# Driver.net
KiCad netlist of a schematic drawn in Altium Designer
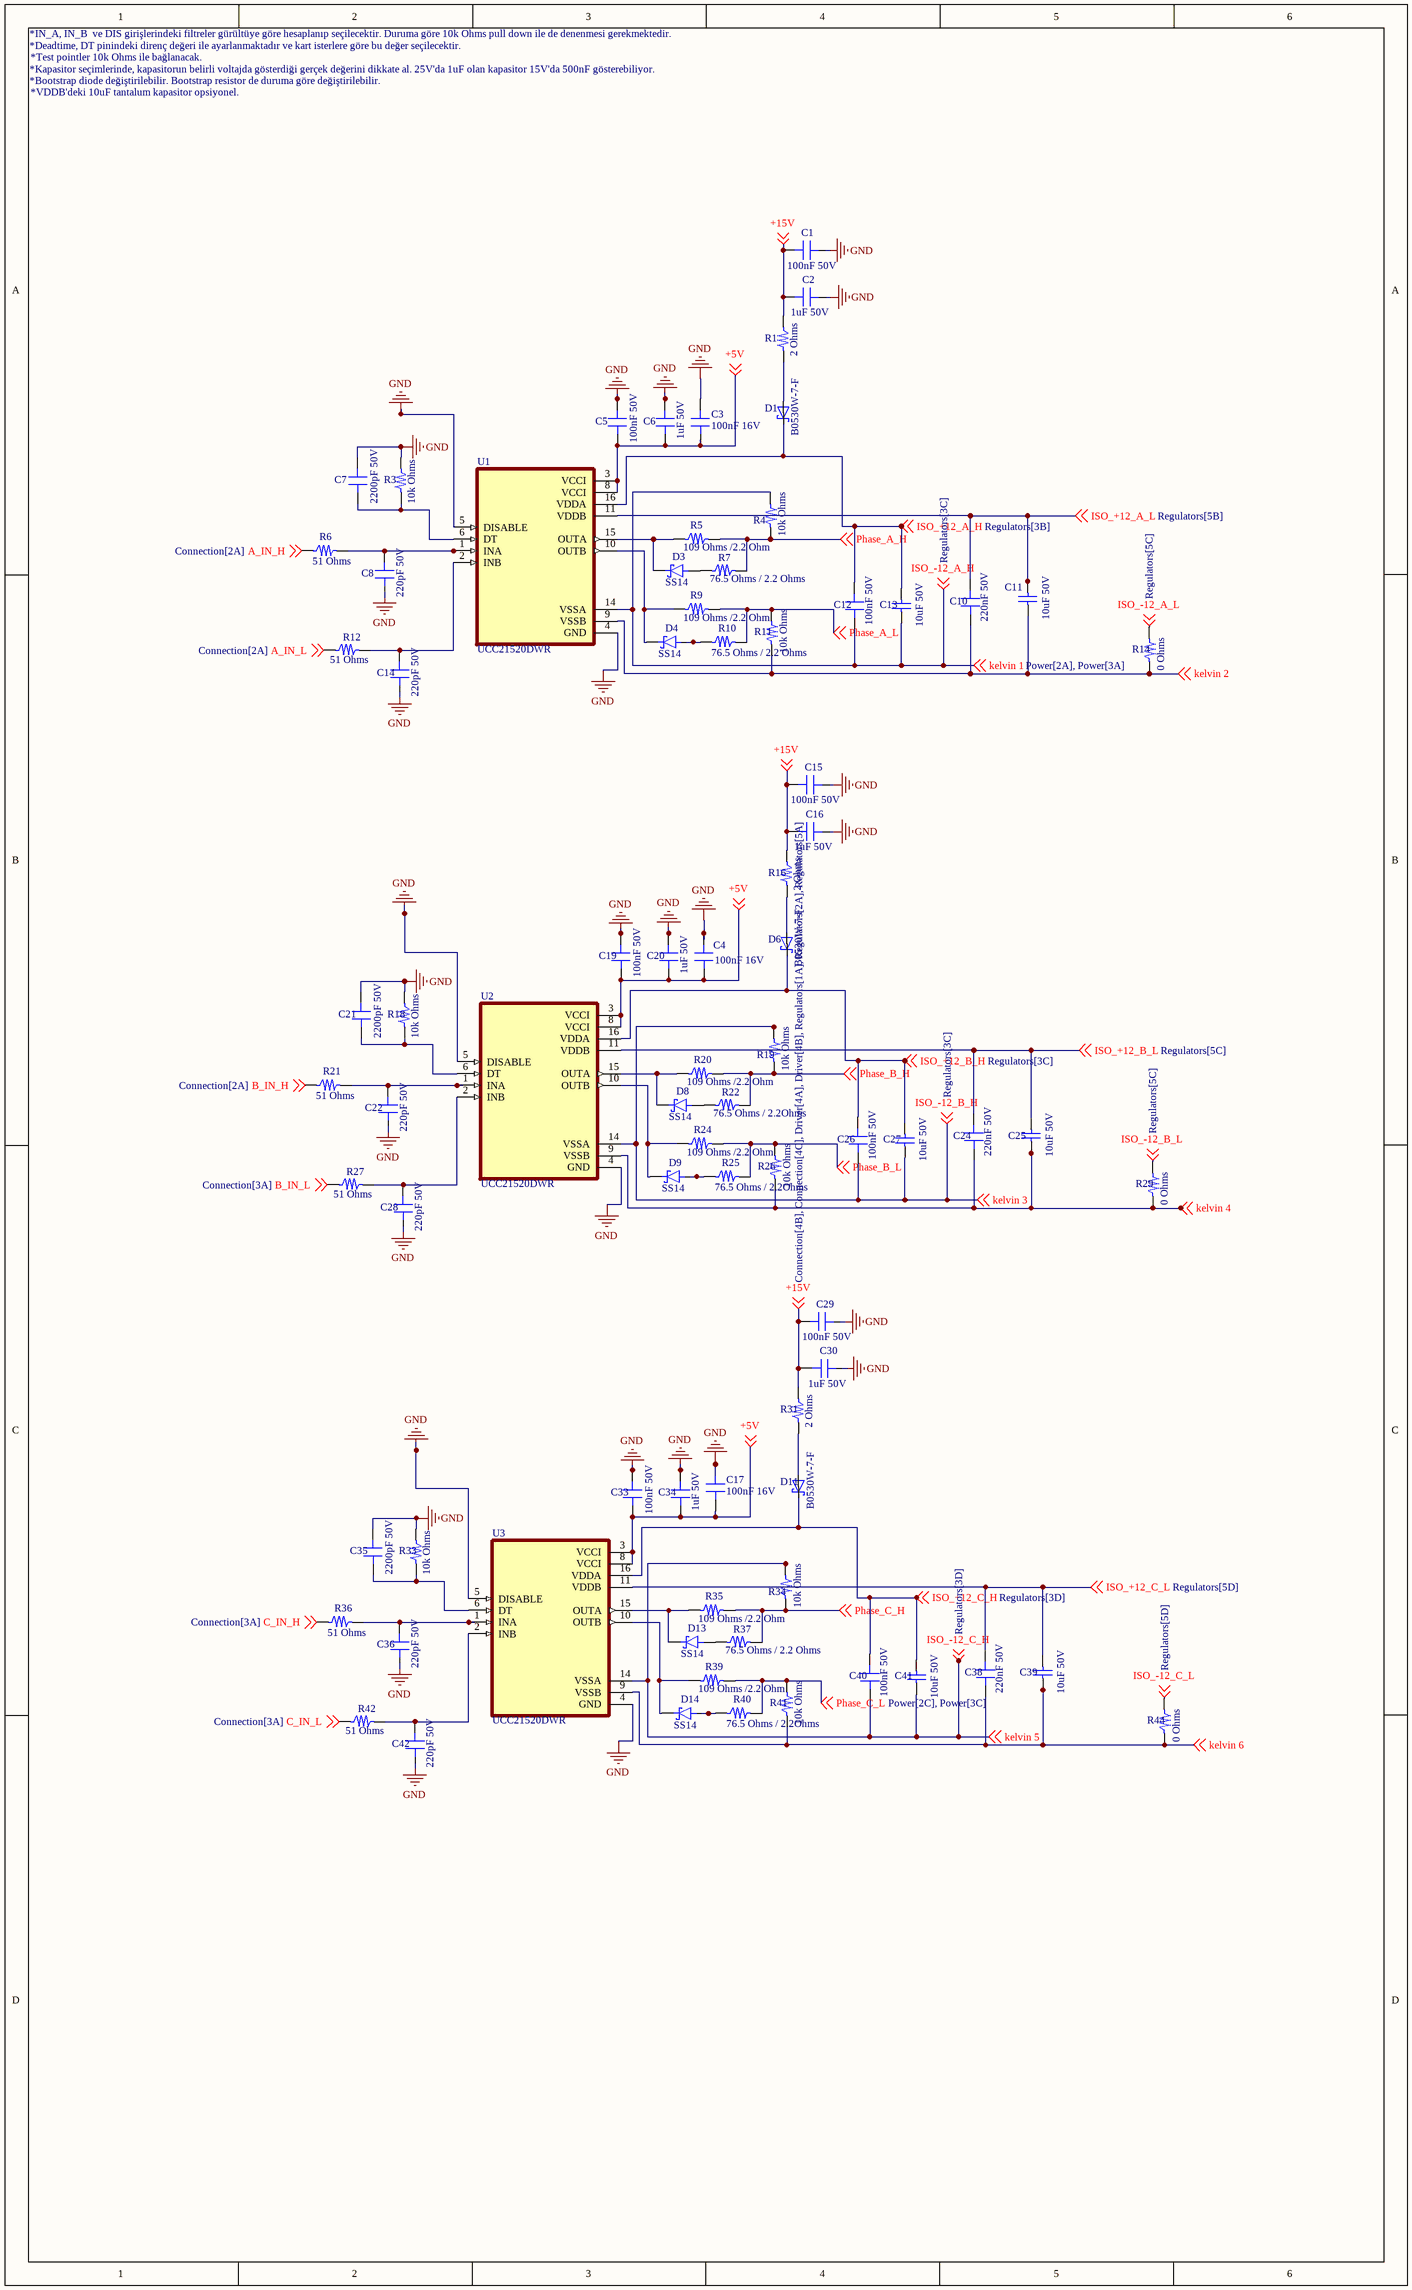
[diagram p0: Driver.SchDoc]

(export (version "E")
  (design (tool "Eeschema 10.0.6"))
  (components
    (comp (ref "C1")
      (value "100nF 50V")
      (footprint "0805_CAP")
      (libsource (lib "HidroanaSCHLib") (part "CAP_0805"))
    )
    (comp (ref "C2")
      (value "1uF 50V")
      (footprint "0805_CAP")
      (libsource (lib "HidroanaSCHLib") (part "CAP_0805"))
    )
    (comp (ref "C3")
      (value "100nF 16V")
      (footprint "0805_CAP")
      (libsource (lib "HidroanaSCHLib1") (part "CAP_0805"))
    )
    (comp (ref "C4")
      (value "100nF 16V")
      (footprint "0805_CAP")
      (libsource (lib "HidroanaSCHLib1") (part "CAP_0805"))
    )
    (comp (ref "C5")
      (value "100nF 50V")
      (footprint "0603_CAP")
      (description "CL10B105KO8NNNC - MLCC (1608) 0603 1uF 16VDC ±10% X7R")
      (libsource (lib "HidroanaSCHLib") (part "CAP_0603"))
    )
    (comp (ref "C6")
      (value "1uF 50V")
      (footprint "0603_CAP")
      (description "CL10B105KO8NNNC - MLCC (1608) 0603 1uF 16VDC ±10% X7R")
      (libsource (lib "HidroanaSCHLib") (part "CAP_0603"))
    )
    (comp (ref "C7")
      (value "2200pF 50V")
      (footprint "0603_CAP")
      (description "CL10B105KO8NNNC - MLCC (1608) 0603 1uF 16VDC ±10% X7R")
      (libsource (lib "HidroanaSCHLib") (part "CAP_0603"))
    )
    (comp (ref "C8")
      (value "220pF 50V")
      (footprint "0603_CAP")
      (description "CL10B105KO8NNNC - MLCC (1608) 0603 1uF 16VDC ±10% X7R")
      (libsource (lib "HidroanaSCHLib") (part "CAP_0603"))
    )
    (comp (ref "C10")
      (value "220nF 50V")
      (footprint "0805_CAP")
      (libsource (lib "HidroanaSCHLib") (part "CAP_0805"))
    )
    (comp (ref "C11")
      (value "10uF 50V")
      (footprint "WCAP-CSGP_1210_L3.2W2.5H0.95")
      (description "WCAP-CSGP Multilayer Ceramic Chip Capacitor, General Purpose, size 1210, NP0, 2.2nF, 50V")
      (fields
        (field (name "MANUFACTURER PART NUMBER") "885012009019")
        (field (name "MANUFACTURER") "Wurth Elektronik")
      )
      (libsource (lib "Altium_WCAP-CSGP (rev24c)") (part "885012009019"))
    )
    (comp (ref "C12")
      (value "100nF 50V")
      (footprint "0805_CAP")
      (libsource (lib "HidroanaSCHLib") (part "CAP_0805"))
    )
    (comp (ref "C13")
      (value "10uF 50V")
      (footprint "WCAP-CSGP_1210_L3.2W2.5H0.95")
      (description "WCAP-CSGP Multilayer Ceramic Chip Capacitor, General Purpose, size 1210, NP0, 2.2nF, 50V")
      (fields
        (field (name "MANUFACTURER PART NUMBER") "885012009019")
        (field (name "MANUFACTURER") "Wurth Elektronik")
      )
      (libsource (lib "Altium_WCAP-CSGP (rev24c)") (part "885012009019"))
    )
    (comp (ref "C14")
      (value "220pF 50V")
      (footprint "0603_CAP")
      (description "CL10B105KO8NNNC - MLCC (1608) 0603 1uF 16VDC ±10% X7R")
      (libsource (lib "HidroanaSCHLib") (part "CAP_0603"))
    )
    (comp (ref "C15")
      (value "100nF 50V")
      (footprint "0805_CAP")
      (libsource (lib "HidroanaSCHLib") (part "CAP_0805"))
    )
    (comp (ref "C16")
      (value "1uF 50V")
      (footprint "0805_CAP")
      (libsource (lib "HidroanaSCHLib") (part "CAP_0805"))
    )
    (comp (ref "C17")
      (value "100nF 16V")
      (footprint "0805_CAP")
      (libsource (lib "HidroanaSCHLib1") (part "CAP_0805"))
    )
    (comp (ref "C19")
      (value "100nF 50V")
      (footprint "0603_CAP")
      (description "CL10B105KO8NNNC - MLCC (1608) 0603 1uF 16VDC ±10% X7R")
      (libsource (lib "HidroanaSCHLib") (part "CAP_0603"))
    )
    (comp (ref "C20")
      (value "1uF 50V")
      (footprint "0603_CAP")
      (description "CL10B105KO8NNNC - MLCC (1608) 0603 1uF 16VDC ±10% X7R")
      (libsource (lib "HidroanaSCHLib") (part "CAP_0603"))
    )
    (comp (ref "C21")
      (value "2200pF 50V")
      (footprint "0603_CAP")
      (description "CL10B105KO8NNNC - MLCC (1608) 0603 1uF 16VDC ±10% X7R")
      (libsource (lib "HidroanaSCHLib") (part "CAP_0603"))
    )
    (comp (ref "C22")
      (value "220pF 50V")
      (footprint "0603_CAP")
      (description "CL10B105KO8NNNC - MLCC (1608) 0603 1uF 16VDC ±10% X7R")
      (libsource (lib "HidroanaSCHLib") (part "CAP_0603"))
    )
    (comp (ref "C24")
      (value "220nF 50V")
      (footprint "0805_CAP")
      (libsource (lib "HidroanaSCHLib") (part "CAP_0805"))
    )
    (comp (ref "C25")
      (value "10uF 50V")
      (footprint "WCAP-CSGP_1210_L3.2W2.5H0.95")
      (description "WCAP-CSGP Multilayer Ceramic Chip Capacitor, General Purpose, size 1210, NP0, 2.2nF, 50V")
      (fields
        (field (name "MANUFACTURER PART NUMBER") "885012009019")
        (field (name "MANUFACTURER") "Wurth Elektronik")
      )
      (libsource (lib "Altium_WCAP-CSGP (rev24c)") (part "885012009019"))
    )
    (comp (ref "C26")
      (value "100nF 50V")
      (footprint "0805_CAP")
      (libsource (lib "HidroanaSCHLib") (part "CAP_0805"))
    )
    (comp (ref "C27")
      (value "10uF 50V")
      (footprint "WCAP-CSGP_1210_L3.2W2.5H0.95")
      (description "WCAP-CSGP Multilayer Ceramic Chip Capacitor, General Purpose, size 1210, NP0, 2.2nF, 50V")
      (fields
        (field (name "MANUFACTURER PART NUMBER") "885012009019")
        (field (name "MANUFACTURER") "Wurth Elektronik")
      )
      (libsource (lib "Altium_WCAP-CSGP (rev24c)") (part "885012009019"))
    )
    (comp (ref "C28")
      (value "220pF 50V")
      (footprint "0603_CAP")
      (description "CL10B105KO8NNNC - MLCC (1608) 0603 1uF 16VDC ±10% X7R")
      (libsource (lib "HidroanaSCHLib") (part "CAP_0603"))
    )
    (comp (ref "C29")
      (value "100nF 50V")
      (footprint "0805_CAP")
      (libsource (lib "HidroanaSCHLib") (part "CAP_0805"))
    )
    (comp (ref "C30")
      (value "1uF 50V")
      (footprint "0805_CAP")
      (libsource (lib "HidroanaSCHLib") (part "CAP_0805"))
    )
    (comp (ref "C33")
      (value "100nF 50V")
      (footprint "0603_CAP")
      (description "CL10B105KO8NNNC - MLCC (1608) 0603 1uF 16VDC ±10% X7R")
      (libsource (lib "HidroanaSCHLib") (part "CAP_0603"))
    )
    (comp (ref "C34")
      (value "1uF 50V")
      (footprint "0603_CAP")
      (description "CL10B105KO8NNNC - MLCC (1608) 0603 1uF 16VDC ±10% X7R")
      (libsource (lib "HidroanaSCHLib") (part "CAP_0603"))
    )
    (comp (ref "C35")
      (value "2200pF 50V")
      (footprint "0603_CAP")
      (description "CL10B105KO8NNNC - MLCC (1608) 0603 1uF 16VDC ±10% X7R")
      (libsource (lib "HidroanaSCHLib") (part "CAP_0603"))
    )
    (comp (ref "C36")
      (value "220pF 50V")
      (footprint "0603_CAP")
      (description "CL10B105KO8NNNC - MLCC (1608) 0603 1uF 16VDC ±10% X7R")
      (libsource (lib "HidroanaSCHLib") (part "CAP_0603"))
    )
    (comp (ref "C38")
      (value "220nF 50V")
      (footprint "0805_CAP")
      (libsource (lib "HidroanaSCHLib") (part "CAP_0805"))
    )
    (comp (ref "C39")
      (value "10uF 50V")
      (footprint "WCAP-CSGP_1210_L3.2W2.5H0.95")
      (description "WCAP-CSGP Multilayer Ceramic Chip Capacitor, General Purpose, size 1210, NP0, 2.2nF, 50V")
      (fields
        (field (name "MANUFACTURER PART NUMBER") "885012009019")
        (field (name "MANUFACTURER") "Wurth Elektronik")
      )
      (libsource (lib "Altium_WCAP-CSGP (rev24c)") (part "885012009019"))
    )
    (comp (ref "C40")
      (value "100nF 50V")
      (footprint "0805_CAP")
      (libsource (lib "HidroanaSCHLib") (part "CAP_0805"))
    )
    (comp (ref "C41")
      (value "10uF 50V")
      (footprint "WCAP-CSGP_1210_L3.2W2.5H0.95")
      (description "WCAP-CSGP Multilayer Ceramic Chip Capacitor, General Purpose, size 1210, NP0, 2.2nF, 50V")
      (fields
        (field (name "MANUFACTURER PART NUMBER") "885012009019")
        (field (name "MANUFACTURER") "Wurth Elektronik")
      )
      (libsource (lib "Altium_WCAP-CSGP (rev24c)") (part "885012009019"))
    )
    (comp (ref "C42")
      (value "220pF 50V")
      (footprint "0603_CAP")
      (description "CL10B105KO8NNNC - MLCC (1608) 0603 1uF 16VDC ±10% X7R")
      (libsource (lib "HidroanaSCHLib") (part "CAP_0603"))
    )
    (comp (ref "D1")
      (value "B0530W-7-F")
      (footprint "DO-214AC")
      (description "Diode Schottky 40 V 1A Surface Mount DO-214AC (SMA)")
      (fields (field (name "MF") "ON Semiconductor") (field (name "MP") "SS14"))
      (libsource (lib "SS14") (part "SS14"))
    )
    (comp (ref "D3")
      (value "SS14")
      (footprint "SOD3715X145N")
      (description "Diode Schottky 30V 500mA Surface Mount SOD-123")
      (fields (field (name "MP") "B0530W-7-F") (field (name "MF") "Diodes Inc."))
      (libsource (lib "B0530W-7-F") (part "B0530W-7-F"))
    )
    (comp (ref "D4")
      (value "SS14")
      (footprint "SOD3715X145N")
      (description "Diode Schottky 30V 500mA Surface Mount SOD-123")
      (fields (field (name "MP") "B0530W-7-F") (field (name "MF") "Diodes Inc."))
      (libsource (lib "B0530W-7-F") (part "B0530W-7-F"))
    )
    (comp (ref "D6")
      (value "B0530W-7-F")
      (footprint "DO-214AC")
      (description "Diode Schottky 40 V 1A Surface Mount DO-214AC (SMA)")
      (fields (field (name "MF") "ON Semiconductor") (field (name "MP") "SS14"))
      (libsource (lib "SS14") (part "SS14"))
    )
    (comp (ref "D8")
      (value "SS14")
      (footprint "SOD3715X145N")
      (description "Diode Schottky 30V 500mA Surface Mount SOD-123")
      (fields (field (name "MP") "B0530W-7-F") (field (name "MF") "Diodes Inc."))
      (libsource (lib "B0530W-7-F") (part "B0530W-7-F"))
    )
    (comp (ref "D9")
      (value "SS14")
      (footprint "SOD3715X145N")
      (description "Diode Schottky 30V 500mA Surface Mount SOD-123")
      (fields (field (name "MP") "B0530W-7-F") (field (name "MF") "Diodes Inc."))
      (libsource (lib "B0530W-7-F") (part "B0530W-7-F"))
    )
    (comp (ref "D11")
      (value "B0530W-7-F")
      (footprint "DO-214AC")
      (description "Diode Schottky 40 V 1A Surface Mount DO-214AC (SMA)")
      (fields (field (name "MF") "ON Semiconductor") (field (name "MP") "SS14"))
      (libsource (lib "SS14") (part "SS14"))
    )
    (comp (ref "D13")
      (value "SS14")
      (footprint "SOD3715X145N")
      (description "Diode Schottky 30V 500mA Surface Mount SOD-123")
      (fields (field (name "MP") "B0530W-7-F") (field (name "MF") "Diodes Inc."))
      (libsource (lib "B0530W-7-F") (part "B0530W-7-F"))
    )
    (comp (ref "D14")
      (value "SS14")
      (footprint "SOD3715X145N")
      (description "Diode Schottky 30V 500mA Surface Mount SOD-123")
      (fields (field (name "MP") "B0530W-7-F") (field (name "MF") "Diodes Inc."))
      (libsource (lib "B0530W-7-F") (part "B0530W-7-F"))
    )
    (comp (ref "R1")
      (value "2 Ohms")
      (footprint "0805_RES")
      (description "0805")
      (fields (field (name "POWER") "1/8 W"))
      (libsource (lib "HidroanaSCHLib") (part "RES_0805"))
    )
    (comp (ref "R3")
      (value "10k Ohms")
      (footprint "0603_RES")
      (libsource (lib "HidroanaSCHLib") (part "1k Ohms"))
    )
    (comp (ref "R4")
      (value "10k Ohms")
      (footprint "0805_RES")
      (description "0805")
      (fields (field (name "POWER") "1/8 W"))
      (libsource (lib "HidroanaSCHLib") (part "RES_0805"))
    )
    (comp (ref "R5")
      (value "109 Ohms /2.2 Ohm")
      (footprint "0805_RES")
      (description "0805")
      (fields (field (name "POWER") "1/8 W"))
      (libsource (lib "HidroanaSCHLib") (part "RES_0805"))
    )
    (comp (ref "R6")
      (value "51 Ohms")
      (footprint "0603_RES")
      (libsource (lib "HidroanaSCHLib") (part "1k Ohms"))
    )
    (comp (ref "R7")
      (value "76.5 Ohms / 2.2 Ohms")
      (footprint "0805_RES")
      (description "0805")
      (fields (field (name "POWER") "1/8 W"))
      (libsource (lib "HidroanaSCHLib") (part "RES_0805"))
    )
    (comp (ref "R9")
      (value "109 Ohms /2.2 Ohm")
      (footprint "0805_RES")
      (description "0805")
      (fields (field (name "POWER") "1/8 W"))
      (libsource (lib "HidroanaSCHLib") (part "RES_0805"))
    )
    (comp (ref "R10")
      (value "76.5 Ohms / 2.2 Ohms")
      (footprint "0805_RES")
      (description "0805")
      (fields (field (name "POWER") "1/8 W"))
      (libsource (lib "HidroanaSCHLib") (part "RES_0805"))
    )
    (comp (ref "R11")
      (value "10k Ohms")
      (footprint "0805_RES")
      (description "0805")
      (fields (field (name "POWER") "1/8 W"))
      (libsource (lib "HidroanaSCHLib") (part "RES_0805"))
    )
    (comp (ref "R12")
      (value "51 Ohms")
      (footprint "0603_RES")
      (libsource (lib "HidroanaSCHLib") (part "1k Ohms"))
    )
    (comp (ref "R14")
      (value "0 Ohms")
      (footprint "0805_RES")
      (description "0805")
      (fields (field (name "POWER") "1/8 W"))
      (libsource (lib "HidroanaSCHLib") (part "RES_0805"))
    )
    (comp (ref "R16")
      (value "2 Ohms")
      (footprint "0805_RES")
      (description "0805")
      (fields (field (name "POWER") "1/8 W"))
      (libsource (lib "HidroanaSCHLib") (part "RES_0805"))
    )
    (comp (ref "R18")
      (value "10k Ohms")
      (footprint "0603_RES")
      (libsource (lib "HidroanaSCHLib") (part "1k Ohms"))
    )
    (comp (ref "R19")
      (value "10k Ohms")
      (footprint "0805_RES")
      (description "0805")
      (fields (field (name "POWER") "1/8 W"))
      (libsource (lib "HidroanaSCHLib") (part "RES_0805"))
    )
    (comp (ref "R20")
      (value "109 Ohms /2.2 Ohm")
      (footprint "0805_RES")
      (description "0805")
      (fields (field (name "POWER") "1/8 W"))
      (libsource (lib "HidroanaSCHLib") (part "RES_0805"))
    )
    (comp (ref "R21")
      (value "51 Ohms")
      (footprint "0603_RES")
      (libsource (lib "HidroanaSCHLib") (part "1k Ohms"))
    )
    (comp (ref "R22")
      (value "76.5 Ohms / 2.2Ohms")
      (footprint "0805_RES")
      (description "0805")
      (fields (field (name "POWER") "1/8 W"))
      (libsource (lib "HidroanaSCHLib") (part "RES_0805"))
    )
    (comp (ref "R24")
      (value "109 Ohms /2.2 Ohm")
      (footprint "0805_RES")
      (description "0805")
      (fields (field (name "POWER") "1/8 W"))
      (libsource (lib "HidroanaSCHLib") (part "RES_0805"))
    )
    (comp (ref "R25")
      (value "76.5 Ohms / 2.2Ohms")
      (footprint "0805_RES")
      (description "0805")
      (fields (field (name "POWER") "1/8 W"))
      (libsource (lib "HidroanaSCHLib") (part "RES_0805"))
    )
    (comp (ref "R26")
      (value "10k Ohms")
      (footprint "0805_RES")
      (description "0805")
      (fields (field (name "POWER") "1/8 W"))
      (libsource (lib "HidroanaSCHLib") (part "RES_0805"))
    )
    (comp (ref "R27")
      (value "51 Ohms")
      (footprint "0603_RES")
      (libsource (lib "HidroanaSCHLib") (part "1k Ohms"))
    )
    (comp (ref "R29")
      (value "0 Ohms")
      (footprint "0805_RES")
      (description "0805")
      (fields (field (name "POWER") "1/8 W"))
      (libsource (lib "HidroanaSCHLib") (part "RES_0805"))
    )
    (comp (ref "R31")
      (value "2 Ohms")
      (footprint "0805_RES")
      (description "0805")
      (fields (field (name "POWER") "1/8 W"))
      (libsource (lib "HidroanaSCHLib") (part "RES_0805"))
    )
    (comp (ref "R33")
      (value "10k Ohms")
      (footprint "0603_RES")
      (libsource (lib "HidroanaSCHLib") (part "1k Ohms"))
    )
    (comp (ref "R34")
      (value "10k Ohms")
      (footprint "0805_RES")
      (description "0805")
      (fields (field (name "POWER") "1/8 W"))
      (libsource (lib "HidroanaSCHLib") (part "RES_0805"))
    )
    (comp (ref "R35")
      (value "109 Ohms /2.2 Ohm")
      (footprint "0805_RES")
      (description "0805")
      (fields (field (name "POWER") "1/8 W"))
      (libsource (lib "HidroanaSCHLib") (part "RES_0805"))
    )
    (comp (ref "R36")
      (value "51 Ohms")
      (footprint "0603_RES")
      (libsource (lib "HidroanaSCHLib") (part "1k Ohms"))
    )
    (comp (ref "R37")
      (value "76.5 Ohms / 2.2 Ohms")
      (footprint "0805_RES")
      (description "0805")
      (fields (field (name "POWER") "1/8 W"))
      (libsource (lib "HidroanaSCHLib") (part "RES_0805"))
    )
    (comp (ref "R39")
      (value "109 Ohms /2.2 Ohm")
      (footprint "0805_RES")
      (description "0805")
      (fields (field (name "POWER") "1/8 W"))
      (libsource (lib "HidroanaSCHLib") (part "RES_0805"))
    )
    (comp (ref "R40")
      (value "76.5 Ohms / 2.2Ohms")
      (footprint "0805_RES")
      (description "0805")
      (fields (field (name "POWER") "1/8 W"))
      (libsource (lib "HidroanaSCHLib") (part "RES_0805"))
    )
    (comp (ref "R41")
      (value "10k Ohms")
      (footprint "0805_RES")
      (description "0805")
      (fields (field (name "POWER") "1/8 W"))
      (libsource (lib "HidroanaSCHLib") (part "RES_0805"))
    )
    (comp (ref "R42")
      (value "51 Ohms")
      (footprint "0603_RES")
      (libsource (lib "HidroanaSCHLib") (part "1k Ohms"))
    )
    (comp (ref "R44")
      (value "0 Ohms")
      (footprint "0805_RES")
      (description "0805")
      (fields (field (name "POWER") "1/8 W"))
      (libsource (lib "HidroanaSCHLib") (part "RES_0805"))
    )
    (comp (ref "U1")
      (value "UCC21520DWR")
      (footprint "SOIC127P1030X265-16N")
      (fields (field (name "MF") "Texas Instruments"))
      (libsource (lib "UCC21520DWR") (part "UCC21520DWR"))
    )
    (comp (ref "U2")
      (value "UCC21520DWR")
      (footprint "SOIC127P1030X265-16N")
      (fields (field (name "MF") "Texas Instruments"))
      (libsource (lib "UCC21520DWR") (part "UCC21520DWR"))
    )
    (comp (ref "U3")
      (value "UCC21520DWR")
      (footprint "SOIC127P1030X265-16N")
      (fields (field (name "MF") "Texas Instruments"))
      (libsource (lib "UCC21520DWR") (part "UCC21520DWR"))
    )
  )
  (nets
    (net (code "1") (name "+5V") (class "Default")
      (node (ref "C17") (pin "2") (pinfunction "2_2") (pintype "passive"))
      (node (ref "C19") (pin "2") (pinfunction "2_2") (pintype "passive"))
      (node (ref "C20") (pin "2") (pinfunction "2_2") (pintype "passive"))
      (node (ref "C3") (pin "2") (pinfunction "2_2") (pintype "passive"))
      (node (ref "C33") (pin "2") (pinfunction "2_2") (pintype "passive"))
      (node (ref "C34") (pin "2") (pinfunction "2_2") (pintype "passive"))
      (node (ref "C4") (pin "2") (pinfunction "2_2") (pintype "passive"))
      (node (ref "C5") (pin "2") (pinfunction "2_2") (pintype "passive"))
      (node (ref "C6") (pin "2") (pinfunction "2_2") (pintype "passive"))
      (node (ref "U1") (pin "3") (pinfunction "VCCI_3") (pintype "power_in"))
      (node (ref "U1") (pin "8") (pinfunction "VCCI_8") (pintype "power_in"))
      (node (ref "U2") (pin "3") (pinfunction "VCCI_3") (pintype "power_in"))
      (node (ref "U2") (pin "8") (pinfunction "VCCI_8") (pintype "power_in"))
      (node (ref "U3") (pin "3") (pinfunction "VCCI_3") (pintype "power_in"))
      (node (ref "U3") (pin "8") (pinfunction "VCCI_8") (pintype "power_in"))
    )
    (net (code "2") (name "+15V") (class "Default")
      (node (ref "C1") (pin "2") (pinfunction "2_2") (pintype "passive"))
      (node (ref "C15") (pin "2") (pinfunction "2_2") (pintype "passive"))
      (node (ref "C16") (pin "2") (pinfunction "2_2") (pintype "passive"))
      (node (ref "C2") (pin "2") (pinfunction "2_2") (pintype "passive"))
      (node (ref "C29") (pin "2") (pinfunction "2_2") (pintype "passive"))
      (node (ref "C30") (pin "2") (pinfunction "2_2") (pintype "passive"))
      (node (ref "R1") (pin "2") (pintype "passive"))
      (node (ref "R16") (pin "2") (pintype "passive"))
      (node (ref "R31") (pin "2") (pintype "passive"))
    )
    (net (code "3") (name "A_IN_H") (class "Default") (node (ref "R6") (pin "1") (pintype "passive")))
    (net (code "4") (name "A_IN_L") (class "Default") (node (ref "R12") (pin "1") (pintype "passive")))
    (net (code "5") (name "B_IN_H") (class "Default") (node (ref "R21") (pin "1") (pintype "passive")))
    (net (code "6") (name "B_IN_L") (class "Default") (node (ref "R27") (pin "1") (pintype "passive")))
    (net (code "7") (name "C_IN_H") (class "Default") (node (ref "R36") (pin "1") (pintype "passive")))
    (net (code "8") (name "C_IN_L") (class "Default") (node (ref "R42") (pin "1") (pintype "passive")))
    (net (code "9") (name "GND") (class "Default")
      (node (ref "C1") (pin "1") (pinfunction "1_1") (pintype "passive"))
      (node (ref "C14") (pin "1") (pinfunction "1_1") (pintype "passive"))
      (node (ref "C15") (pin "1") (pinfunction "1_1") (pintype "passive"))
      (node (ref "C16") (pin "1") (pinfunction "1_1") (pintype "passive"))
      (node (ref "C17") (pin "1") (pinfunction "1_1") (pintype "passive"))
      (node (ref "C19") (pin "1") (pinfunction "1_1") (pintype "passive"))
      (node (ref "C2") (pin "1") (pinfunction "1_1") (pintype "passive"))
      (node (ref "C20") (pin "1") (pinfunction "1_1") (pintype "passive"))
      (node (ref "C21") (pin "2") (pinfunction "2_2") (pintype "passive"))
      (node (ref "C22") (pin "1") (pinfunction "1_1") (pintype "passive"))
      (node (ref "C28") (pin "1") (pinfunction "1_1") (pintype "passive"))
      (node (ref "C29") (pin "1") (pinfunction "1_1") (pintype "passive"))
      (node (ref "C3") (pin "1") (pinfunction "1_1") (pintype "passive"))
      (node (ref "C30") (pin "1") (pinfunction "1_1") (pintype "passive"))
      (node (ref "C33") (pin "1") (pinfunction "1_1") (pintype "passive"))
      (node (ref "C34") (pin "1") (pinfunction "1_1") (pintype "passive"))
      (node (ref "C35") (pin "2") (pinfunction "2_2") (pintype "passive"))
      (node (ref "C36") (pin "1") (pinfunction "1_1") (pintype "passive"))
      (node (ref "C4") (pin "1") (pinfunction "1_1") (pintype "passive"))
      (node (ref "C42") (pin "1") (pinfunction "1_1") (pintype "passive"))
      (node (ref "C5") (pin "1") (pinfunction "1_1") (pintype "passive"))
      (node (ref "C6") (pin "1") (pinfunction "1_1") (pintype "passive"))
      (node (ref "C7") (pin "2") (pinfunction "2_2") (pintype "passive"))
      (node (ref "C8") (pin "1") (pinfunction "1_1") (pintype "passive"))
      (node (ref "R18") (pin "2") (pintype "passive"))
      (node (ref "R3") (pin "2") (pintype "passive"))
      (node (ref "R33") (pin "2") (pintype "passive"))
      (node (ref "U1") (pin "4") (pinfunction "GND_4") (pintype "power_in"))
      (node (ref "U1") (pin "5") (pinfunction "DISABLE_5") (pintype "input"))
      (node (ref "U2") (pin "4") (pinfunction "GND_4") (pintype "power_in"))
      (node (ref "U2") (pin "5") (pinfunction "DISABLE_5") (pintype "input"))
      (node (ref "U3") (pin "4") (pinfunction "GND_4") (pintype "power_in"))
      (node (ref "U3") (pin "5") (pinfunction "DISABLE_5") (pintype "input"))
    )
    (net (code "10") (name "ISO_+12_A_H") (class "Default")
      (node (ref "C12") (pin "1") (pinfunction "1_1") (pintype "passive"))
      (node (ref "C13") (pin "2") (pinfunction "2_2") (pintype "passive"))
      (node (ref "D1") (pin "K") (pinfunction "K_K") (pintype "passive"))
      (node (ref "U1") (pin "16") (pinfunction "VDDA_16") (pintype "power_in"))
    )
    (net (code "11") (name "ISO_+12_A_L") (class "Default")
      (node (ref "C10") (pin "1") (pinfunction "1_1") (pintype "passive"))
      (node (ref "C11") (pin "2") (pinfunction "2_2") (pintype "passive"))
      (node (ref "U1") (pin "11") (pinfunction "VDDB_11") (pintype "power_in"))
    )
    (net (code "12") (name "ISO_+12_B_H") (class "Default")
      (node (ref "C26") (pin "1") (pinfunction "1_1") (pintype "passive"))
      (node (ref "C27") (pin "2") (pinfunction "2_2") (pintype "passive"))
      (node (ref "D6") (pin "K") (pinfunction "K_K") (pintype "passive"))
      (node (ref "U2") (pin "16") (pinfunction "VDDA_16") (pintype "power_in"))
    )
    (net (code "13") (name "ISO_+12_B_L") (class "Default")
      (node (ref "C24") (pin "1") (pinfunction "1_1") (pintype "passive"))
      (node (ref "C25") (pin "2") (pinfunction "2_2") (pintype "passive"))
      (node (ref "U2") (pin "11") (pinfunction "VDDB_11") (pintype "power_in"))
    )
    (net (code "14") (name "ISO_+12_C_H") (class "Default")
      (node (ref "C40") (pin "1") (pinfunction "1_1") (pintype "passive"))
      (node (ref "C41") (pin "2") (pinfunction "2_2") (pintype "passive"))
      (node (ref "D11") (pin "K") (pinfunction "K_K") (pintype "passive"))
      (node (ref "U3") (pin "16") (pinfunction "VDDA_16") (pintype "power_in"))
    )
    (net (code "15") (name "ISO_+12_C_L") (class "Default")
      (node (ref "C38") (pin "1") (pinfunction "1_1") (pintype "passive"))
      (node (ref "C39") (pin "2") (pinfunction "2_2") (pintype "passive"))
      (node (ref "U3") (pin "11") (pinfunction "VDDB_11") (pintype "power_in"))
    )
    (net (code "16") (name "ISO_-12_A_H") (class "Default")
      (node (ref "C12") (pin "2") (pinfunction "2_2") (pintype "passive"))
      (node (ref "C13") (pin "1") (pinfunction "1_1") (pintype "passive"))
      (node (ref "R4") (pin "1") (pintype "passive"))
      (node (ref "U1") (pin "14") (pinfunction "VSSA_14") (pintype "power_in"))
    )
    (net (code "17") (name "ISO_-12_A_L") (class "Default") (node (ref "R14") (pin "1") (pintype "passive")))
    (net (code "18") (name "ISO_-12_B_H") (class "Default")
      (node (ref "C26") (pin "2") (pinfunction "2_2") (pintype "passive"))
      (node (ref "C27") (pin "1") (pinfunction "1_1") (pintype "passive"))
      (node (ref "R19") (pin "1") (pintype "passive"))
      (node (ref "U2") (pin "14") (pinfunction "VSSA_14") (pintype "power_in"))
    )
    (net (code "19") (name "ISO_-12_B_L") (class "Default") (node (ref "R29") (pin "1") (pintype "passive")))
    (net (code "20") (name "ISO_-12_C_H") (class "Default")
      (node (ref "C40") (pin "2") (pinfunction "2_2") (pintype "passive"))
      (node (ref "C41") (pin "1") (pinfunction "1_1") (pintype "passive"))
      (node (ref "R34") (pin "1") (pintype "passive"))
      (node (ref "U3") (pin "14") (pinfunction "VSSA_14") (pintype "power_in"))
    )
    (net (code "21") (name "ISO_-12_C_L") (class "Default") (node (ref "R44") (pin "1") (pintype "passive")))
    (net (code "22") (name "Net-(D1-PadA)") (class "Default")
      (node (ref "D1") (pin "A") (pinfunction "A_A") (pintype "passive"))
      (node (ref "R1") (pin "1") (pintype "passive"))
    )
    (net (code "23") (name "Net-(D3-PadA)") (class "Default")
      (node (ref "D3") (pin "A") (pinfunction "A_A") (pintype "passive"))
      (node (ref "R7") (pin "1") (pintype "passive"))
    )
    (net (code "24") (name "Net-(D4-PadA)") (class "Default")
      (node (ref "D4") (pin "A") (pinfunction "A_A") (pintype "passive"))
      (node (ref "R10") (pin "1") (pintype "passive"))
    )
    (net (code "25") (name "Net-(D6-PadA)") (class "Default")
      (node (ref "D6") (pin "A") (pinfunction "A_A") (pintype "passive"))
      (node (ref "R16") (pin "1") (pintype "passive"))
    )
    (net (code "26") (name "Net-(D8-PadA)") (class "Default")
      (node (ref "D8") (pin "A") (pinfunction "A_A") (pintype "passive"))
      (node (ref "R22") (pin "1") (pintype "passive"))
    )
    (net (code "27") (name "Net-(D9-PadA)") (class "Default")
      (node (ref "D9") (pin "A") (pinfunction "A_A") (pintype "passive"))
      (node (ref "R25") (pin "1") (pintype "passive"))
    )
    (net (code "28") (name "Net-(D11-PadA)") (class "Default")
      (node (ref "D11") (pin "A") (pinfunction "A_A") (pintype "passive"))
      (node (ref "R31") (pin "1") (pintype "passive"))
    )
    (net (code "29") (name "Net-(D13-PadA)") (class "Default")
      (node (ref "D13") (pin "A") (pinfunction "A_A") (pintype "passive"))
      (node (ref "R37") (pin "1") (pintype "passive"))
    )
    (net (code "30") (name "Net-(D14-PadA)") (class "Default")
      (node (ref "D14") (pin "A") (pinfunction "A_A") (pintype "passive"))
      (node (ref "R40") (pin "1") (pintype "passive"))
    )
    (net (code "31") (name "Net-(U1-DT)") (class "Default")
      (node (ref "C7") (pin "1") (pinfunction "1_1") (pintype "passive"))
      (node (ref "R3") (pin "1") (pintype "passive"))
      (node (ref "U1") (pin "6") (pinfunction "DT_6") (pintype "input"))
    )
    (net (code "32") (name "Net-(U1-INA)") (class "Default")
      (node (ref "C8") (pin "2") (pinfunction "2_2") (pintype "passive"))
      (node (ref "R6") (pin "2") (pintype "passive"))
      (node (ref "U1") (pin "1") (pinfunction "INA_1") (pintype "input"))
    )
    (net (code "33") (name "Net-(U1-INB)") (class "Default")
      (node (ref "C14") (pin "2") (pinfunction "2_2") (pintype "passive"))
      (node (ref "R12") (pin "2") (pintype "passive"))
      (node (ref "U1") (pin "2") (pinfunction "INB_2") (pintype "input"))
    )
    (net (code "34") (name "Net-(U1-OUTA)") (class "Default")
      (node (ref "D3") (pin "C") (pinfunction "C_C") (pintype "passive"))
      (node (ref "R5") (pin "1") (pintype "passive"))
      (node (ref "U1") (pin "15") (pinfunction "OUTA_15") (pintype "output"))
    )
    (net (code "35") (name "Net-(U1-OUTB)") (class "Default")
      (node (ref "D4") (pin "C") (pinfunction "C_C") (pintype "passive"))
      (node (ref "R9") (pin "1") (pintype "passive"))
      (node (ref "U1") (pin "10") (pinfunction "OUTB_10") (pintype "output"))
    )
    (net (code "36") (name "Net-(U2-DT)") (class "Default")
      (node (ref "C21") (pin "1") (pinfunction "1_1") (pintype "passive"))
      (node (ref "R18") (pin "1") (pintype "passive"))
      (node (ref "U2") (pin "6") (pinfunction "DT_6") (pintype "input"))
    )
    (net (code "37") (name "Net-(U2-INA)") (class "Default")
      (node (ref "C22") (pin "2") (pinfunction "2_2") (pintype "passive"))
      (node (ref "R21") (pin "2") (pintype "passive"))
      (node (ref "U2") (pin "1") (pinfunction "INA_1") (pintype "input"))
    )
    (net (code "38") (name "Net-(U2-INB)") (class "Default")
      (node (ref "C28") (pin "2") (pinfunction "2_2") (pintype "passive"))
      (node (ref "R27") (pin "2") (pintype "passive"))
      (node (ref "U2") (pin "2") (pinfunction "INB_2") (pintype "input"))
    )
    (net (code "39") (name "Net-(U2-OUTA)") (class "Default")
      (node (ref "D8") (pin "C") (pinfunction "C_C") (pintype "passive"))
      (node (ref "R20") (pin "1") (pintype "passive"))
      (node (ref "U2") (pin "15") (pinfunction "OUTA_15") (pintype "output"))
    )
    (net (code "40") (name "Net-(U2-OUTB)") (class "Default")
      (node (ref "D9") (pin "C") (pinfunction "C_C") (pintype "passive"))
      (node (ref "R24") (pin "1") (pintype "passive"))
      (node (ref "U2") (pin "10") (pinfunction "OUTB_10") (pintype "output"))
    )
    (net (code "41") (name "Net-(U3-DT)") (class "Default")
      (node (ref "C35") (pin "1") (pinfunction "1_1") (pintype "passive"))
      (node (ref "R33") (pin "1") (pintype "passive"))
      (node (ref "U3") (pin "6") (pinfunction "DT_6") (pintype "input"))
    )
    (net (code "42") (name "Net-(U3-INA)") (class "Default")
      (node (ref "C36") (pin "2") (pinfunction "2_2") (pintype "passive"))
      (node (ref "R36") (pin "2") (pintype "passive"))
      (node (ref "U3") (pin "1") (pinfunction "INA_1") (pintype "input"))
    )
    (net (code "43") (name "Net-(U3-INB)") (class "Default")
      (node (ref "C42") (pin "2") (pinfunction "2_2") (pintype "passive"))
      (node (ref "R42") (pin "2") (pintype "passive"))
      (node (ref "U3") (pin "2") (pinfunction "INB_2") (pintype "input"))
    )
    (net (code "44") (name "Net-(U3-OUTA)") (class "Default")
      (node (ref "D13") (pin "C") (pinfunction "C_C") (pintype "passive"))
      (node (ref "R35") (pin "1") (pintype "passive"))
      (node (ref "U3") (pin "15") (pinfunction "OUTA_15") (pintype "output"))
    )
    (net (code "45") (name "Net-(U3-OUTB)") (class "Default")
      (node (ref "D14") (pin "C") (pinfunction "C_C") (pintype "passive"))
      (node (ref "R39") (pin "1") (pintype "passive"))
      (node (ref "U3") (pin "10") (pinfunction "OUTB_10") (pintype "output"))
    )
    (net (code "46") (name "Phase_A_H") (class "Default")
      (node (ref "R4") (pin "2") (pintype "passive"))
      (node (ref "R5") (pin "2") (pintype "passive"))
      (node (ref "R7") (pin "2") (pintype "passive"))
    )
    (net (code "47") (name "Phase_A_L") (class "Default")
      (node (ref "R10") (pin "2") (pintype "passive"))
      (node (ref "R11") (pin "1") (pintype "passive"))
      (node (ref "R9") (pin "2") (pintype "passive"))
    )
    (net (code "48") (name "Phase_B_H") (class "Default")
      (node (ref "R19") (pin "2") (pintype "passive"))
      (node (ref "R20") (pin "2") (pintype "passive"))
      (node (ref "R22") (pin "2") (pintype "passive"))
    )
    (net (code "49") (name "Phase_B_L") (class "Default")
      (node (ref "R24") (pin "2") (pintype "passive"))
      (node (ref "R25") (pin "2") (pintype "passive"))
      (node (ref "R26") (pin "1") (pintype "passive"))
    )
    (net (code "50") (name "Phase_C_H") (class "Default")
      (node (ref "R34") (pin "2") (pintype "passive"))
      (node (ref "R35") (pin "2") (pintype "passive"))
      (node (ref "R37") (pin "2") (pintype "passive"))
    )
    (net (code "51") (name "Phase_C_L") (class "Default")
      (node (ref "R39") (pin "2") (pintype "passive"))
      (node (ref "R40") (pin "2") (pintype "passive"))
      (node (ref "R41") (pin "1") (pintype "passive"))
    )
    (net (code "52") (name "kelvin 2") (class "Default")
      (node (ref "C10") (pin "2") (pinfunction "2_2") (pintype "passive"))
      (node (ref "C11") (pin "1") (pinfunction "1_1") (pintype "passive"))
      (node (ref "R11") (pin "2") (pintype "passive"))
      (node (ref "R14") (pin "2") (pintype "passive"))
      (node (ref "U1") (pin "9") (pinfunction "VSSB_9") (pintype "power_in"))
    )
    (net (code "53") (name "kelvin 4") (class "Default")
      (node (ref "C24") (pin "2") (pinfunction "2_2") (pintype "passive"))
      (node (ref "C25") (pin "1") (pinfunction "1_1") (pintype "passive"))
      (node (ref "R26") (pin "2") (pintype "passive"))
      (node (ref "R29") (pin "2") (pintype "passive"))
      (node (ref "U2") (pin "9") (pinfunction "VSSB_9") (pintype "power_in"))
    )
    (net (code "54") (name "kelvin 6") (class "Default")
      (node (ref "C38") (pin "2") (pinfunction "2_2") (pintype "passive"))
      (node (ref "C39") (pin "1") (pinfunction "1_1") (pintype "passive"))
      (node (ref "R41") (pin "2") (pintype "passive"))
      (node (ref "R44") (pin "2") (pintype "passive"))
      (node (ref "U3") (pin "9") (pinfunction "VSSB_9") (pintype "power_in"))
    )
  )
)
